# USBInterface.net
KiCad netlist of a schematic drawn in Altium Designer
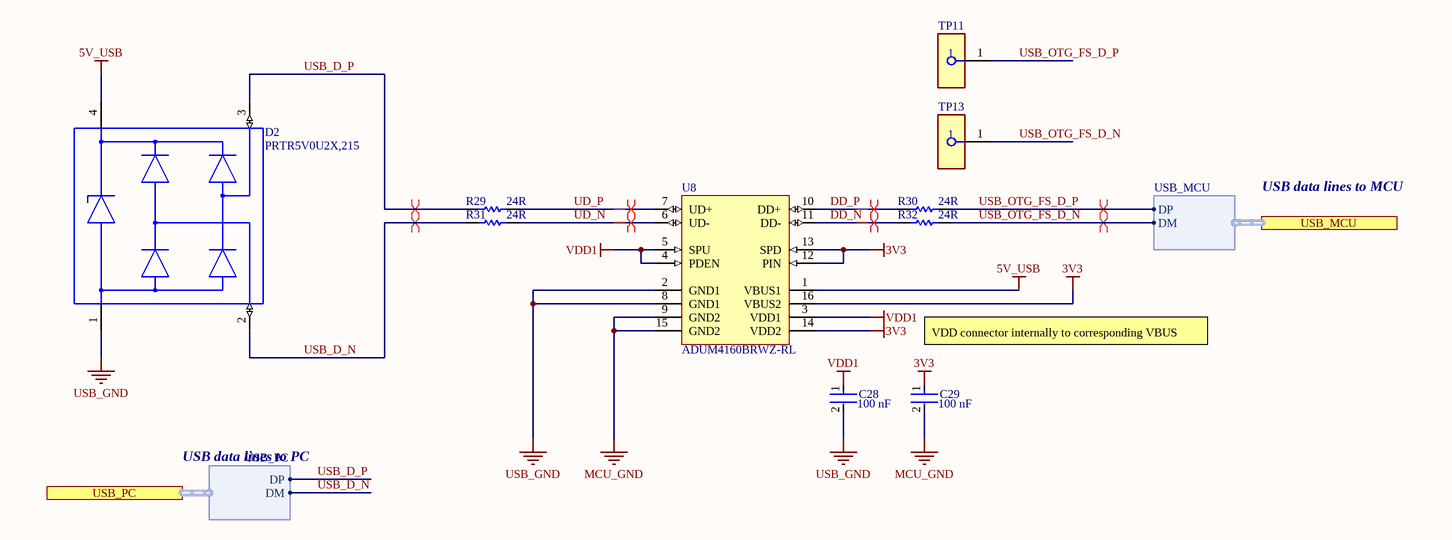
[diagram p0: USBInterface.SchDoc]

(export (version "E")
  (design (tool "Eeschema 10.0.6"))
  (components
    (comp (ref "C28")
      (value "CC0603KRX7R7BB104")
      (footprint "FP-CC0603-DA-MFG")
      (description "CAP CER 0.1UF 16V X7R 0603")
      (fields
        (field (name "OCTOPART") "https://octopart.com/cc0603krx7r7bb104-yageo-192941")
        (field (name "TOLERANCE") "0.1")
        (field (name "CAPACITANCE") "100 nF")
      )
      (libsource (lib "Altium Content Vault") (part "11868f565c42a9108669ba33697ecf6"))
    )
    (comp (ref "C29")
      (value "CC0603KRX7R7BB104")
      (footprint "FP-CC0603-DA-MFG")
      (description "CAP CER 0.1UF 16V X7R 0603")
      (fields
        (field (name "OCTOPART") "https://octopart.com/cc0603krx7r7bb104-yageo-192941")
        (field (name "TOLERANCE") "0.1")
        (field (name "CAPACITANCE") "100 nF")
      )
      (libsource (lib "Altium Content Vault") (part "11868f565c42a9108669ba33697ecf6"))
    )
    (comp (ref "D2")
      (value "PRTR5V0U2X,215")
      (footprint "FP-SOT143B-MFG")
      (description "TVS DIODE 5.5V SOT143B")
      (libsource (lib "Altium Content Vault") (part "31e4fa1655694efd507c8a671e666ef"))
    )
    (comp (ref "R29")
      (value "ERJ-3EKF24R0V")
      (footprint "RESC1608X55X30ML15T15")
      (fields (field (name "MANUFACTURER") "Panasonic") (field (name "RESISTANCE") "24R"))
      (libsource (lib "Altium Content Vault") (part "RES"))
    )
    (comp (ref "R30")
      (value "ERJ-3EKF24R0V")
      (footprint "RESC1608X55X30ML15T15")
      (fields (field (name "MANUFACTURER") "Panasonic") (field (name "RESISTANCE") "24R"))
      (libsource (lib "Altium Content Vault") (part "RES"))
    )
    (comp (ref "R31")
      (value "ERJ-3EKF24R0V")
      (footprint "RESC1608X55X30ML15T15")
      (fields (field (name "MANUFACTURER") "Panasonic") (field (name "RESISTANCE") "24R"))
      (libsource (lib "Altium Content Vault") (part "RES"))
    )
    (comp (ref "R32")
      (value "ERJ-3EKF24R0V")
      (footprint "RESC1608X55X30ML15T15")
      (fields (field (name "MANUFACTURER") "Panasonic") (field (name "RESISTANCE") "24R"))
      (libsource (lib "Altium Content Vault") (part "RES"))
    )
    (comp (ref "TP11")
      (value "S2761-46R")
      (footprint "FP-S2761-46R-MFG")
      (description "PC TEST POINT NATURAL")
      (libsource (lib "Altium Content Vault") (part "98815daf2f2c152b0c43f5ab9800df6"))
    )
    (comp (ref "TP13")
      (value "S2761-46R")
      (footprint "FP-S2761-46R-MFG")
      (description "PC TEST POINT NATURAL")
      (libsource (lib "Altium Content Vault") (part "98815daf2f2c152b0c43f5ab9800df6"))
    )
    (comp (ref "U8")
      (value "ADUM4160BRWZ-RL")
      (footprint "RW-16_L")
      (fields (field (name "MANUFACTURER") "Analog Devices"))
      (libsource (lib "Altium Content Vault") (part "ADI-ADUM4160-16"))
    )
  )
  (nets
    (net (code "3") (name "/DD_N") (class "Default")
      (node (ref "R32") (pin "1") (pinfunction "1_1") (pintype "passive"))
      (node (ref "U8") (pin "11") (pinfunction "DD-_11") (pintype "bidirectional"))
    )
    (net (code "4") (name "/DD_P") (class "Default")
      (node (ref "R30") (pin "1") (pinfunction "1_1") (pintype "passive"))
      (node (ref "U8") (pin "10") (pinfunction "DD+_10") (pintype "bidirectional"))
    )
    (net (code "5") (name "/UD_N") (class "Default")
      (node (ref "R31") (pin "2") (pinfunction "2_2") (pintype "passive"))
      (node (ref "U8") (pin "6") (pinfunction "UD-_6") (pintype "bidirectional"))
    )
    (net (code "6") (name "/UD_P") (class "Default")
      (node (ref "R29") (pin "2") (pinfunction "2_2") (pintype "passive"))
      (node (ref "U8") (pin "7") (pinfunction "UD+_7") (pintype "bidirectional"))
    )
    (net (code "7") (name "/USB_D_N") (class "Default")
      (node (ref "D2") (pin "2") (pinfunction "I/O_1_2") (pintype "bidirectional"))
      (node (ref "R31") (pin "1") (pinfunction "1_1") (pintype "passive"))
    )
    (net (code "8") (name "/USB_D_P") (class "Default")
      (node (ref "D2") (pin "3") (pinfunction "I/O_2_3") (pintype "bidirectional"))
      (node (ref "R29") (pin "1") (pinfunction "1_1") (pintype "passive"))
    )
    (net (code "9") (name "/USB_OTG_FS_D_N") (class "Default")
      (node (ref "R32") (pin "2") (pinfunction "2_2") (pintype "passive"))
      (node (ref "TP13") (pin "1") (pinfunction "1_1") (pintype "passive"))
    )
    (net (code "10") (name "/USB_OTG_FS_D_P") (class "Default")
      (node (ref "R30") (pin "2") (pinfunction "2_2") (pintype "passive"))
      (node (ref "TP11") (pin "1") (pinfunction "1_1") (pintype "passive"))
    )
    (net (code "13") (name "3V3") (class "Default")
      (node (ref "C29") (pin "1") (pinfunction "1_1") (pintype "passive"))
      (node (ref "U8") (pin "12") (pinfunction "PIN_12") (pintype "input"))
      (node (ref "U8") (pin "13") (pinfunction "SPD_13") (pintype "input"))
      (node (ref "U8") (pin "14") (pinfunction "VDD2_14") (pintype "power_in"))
      (node (ref "U8") (pin "16") (pinfunction "VBUS2_16") (pintype "power_in"))
    )
    (net (code "14") (name "5V_USB") (class "Default")
      (node (ref "D2") (pin "4") (pinfunction "VCC_4") (pintype "power_in"))
      (node (ref "U8") (pin "1") (pinfunction "VBUS1_1") (pintype "power_in"))
    )
    (net (code "15") (name "MCU_GND") (class "Default")
      (node (ref "C29") (pin "2") (pinfunction "2_2") (pintype "passive"))
      (node (ref "U8") (pin "15") (pinfunction "GND2_15") (pintype "power_in"))
      (node (ref "U8") (pin "9") (pinfunction "GND2_9") (pintype "power_in"))
    )
    (net (code "16") (name "USB_GND") (class "Default")
      (node (ref "C28") (pin "2") (pinfunction "2_2") (pintype "passive"))
      (node (ref "D2") (pin "1") (pinfunction "GND_1") (pintype "power_in"))
      (node (ref "U8") (pin "2") (pinfunction "GND1_2") (pintype "power_in"))
      (node (ref "U8") (pin "8") (pinfunction "GND1_8") (pintype "power_in"))
    )
    (net (code "17") (name "VDD1") (class "Default")
      (node (ref "C28") (pin "1") (pinfunction "1_1") (pintype "passive"))
      (node (ref "U8") (pin "3") (pinfunction "VDD1_3") (pintype "power_in"))
      (node (ref "U8") (pin "4") (pinfunction "PDEN_4") (pintype "input"))
      (node (ref "U8") (pin "5") (pinfunction "SPU_5") (pintype "input"))
    )
  )
)
